# Door_switch.net
KiCad netlist of a schematic drawn in EAGLE
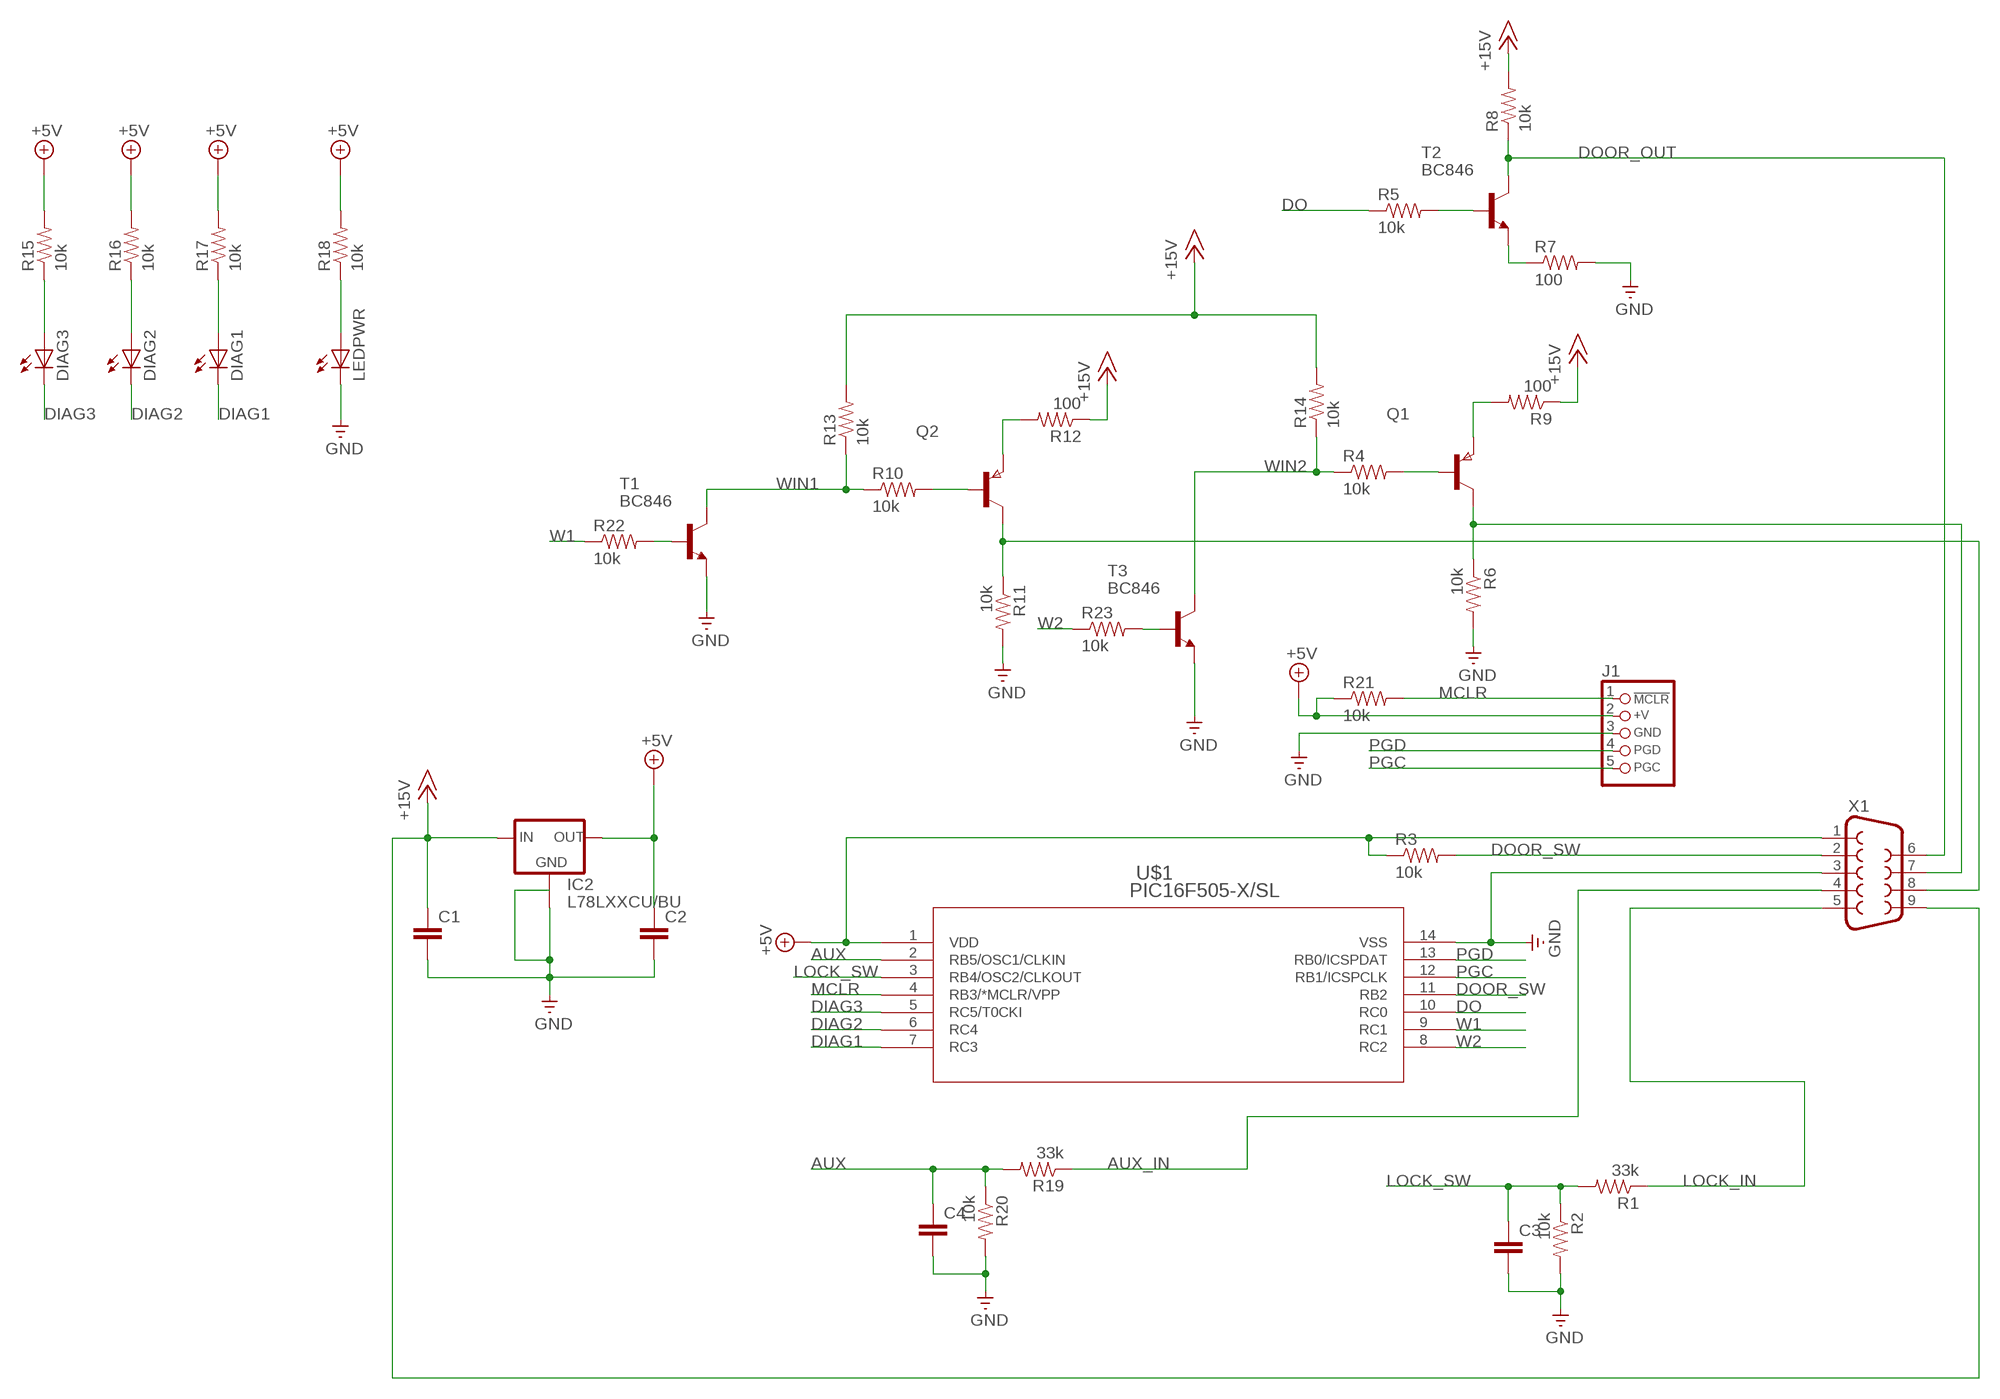
[diagram p0: schematic, sheet 1]

(export (version "E")
  (design (tool "Eeschema 10.0.6"))
  (components
    (comp (ref "C1")
      (value "CC1206")
      (footprint "eagle-import:C1206")
      (libsource (lib "eagle-import") (part "CC1206"))
    )
    (comp (ref "C2")
      (value "CC1206")
      (footprint "eagle-import:C1206")
      (libsource (lib "eagle-import") (part "CC1206"))
    )
    (comp (ref "C3")
      (value "CC1206")
      (footprint "eagle-import:C1206")
      (libsource (lib "eagle-import") (part "CC1206"))
    )
    (comp (ref "C4")
      (value "CC1206")
      (footprint "eagle-import:C1206")
      (libsource (lib "eagle-import") (part "CC1206"))
    )
    (comp (ref "DIAG1")
      (value "LEDCHIP-LED0603")
      (footprint "eagle-import:CHIP-LED0603")
      (libsource (lib "eagle-import") (part "LEDCHIP-LED0603"))
    )
    (comp (ref "DIAG2")
      (value "LEDCHIP-LED0603")
      (footprint "eagle-import:CHIP-LED0603")
      (libsource (lib "eagle-import") (part "LEDCHIP-LED0603"))
    )
    (comp (ref "DIAG3")
      (value "LEDCHIP-LED0603")
      (footprint "eagle-import:CHIP-LED0603")
      (libsource (lib "eagle-import") (part "LEDCHIP-LED0603"))
    )
    (comp (ref "IC2")
      (value "L78LXXCU/BU")
      (footprint "eagle-import:SOT89")
      (libsource (lib "eagle-import") (part "L78LXXCU/BU"))
    )
    (comp (ref "J1")
      (value "CON_HEADER_PRG_PIC_ICSPA")
      (footprint "eagle-import:HEADER_PRG_1X05")
      (libsource (lib "eagle-import") (part "CON_HEADER_PRG_PIC_ICSPA"))
    )
    (comp (ref "LEDPWR")
      (value "LEDCHIP-LED0603")
      (footprint "eagle-import:CHIP-LED0603")
      (libsource (lib "eagle-import") (part "LEDCHIP-LED0603"))
    )
    (comp (ref "Q1")
      (value "PNPSOT23")
      (footprint "eagle-import:SOT-23")
      (fields (field (name "MPN") "DSS20200L-7"))
      (libsource (lib "eagle-import") (part "PNPSOT23"))
    )
    (comp (ref "Q2")
      (value "PNPSOT23")
      (footprint "eagle-import:SOT-23")
      (fields (field (name "MPN") "DSS20200L-7"))
      (libsource (lib "eagle-import") (part "PNPSOT23"))
    )
    (comp (ref "R1")
      (value "33k")
      (footprint "eagle-import:0603-RES")
      (libsource (lib "eagle-import") (part "RESISTOR0603-RES"))
    )
    (comp (ref "R2")
      (value "10k")
      (footprint "eagle-import:0603-RES")
      (libsource (lib "eagle-import") (part "RESISTOR0603-RES"))
    )
    (comp (ref "R3")
      (value "10k")
      (footprint "eagle-import:0603-RES")
      (libsource (lib "eagle-import") (part "RESISTOR0603-RES"))
    )
    (comp (ref "R4")
      (value "10k")
      (footprint "eagle-import:0603-RES")
      (libsource (lib "eagle-import") (part "RESISTOR0603-RES"))
    )
    (comp (ref "R5")
      (value "10k")
      (footprint "eagle-import:0603-RES")
      (libsource (lib "eagle-import") (part "RESISTOR0603-RES"))
    )
    (comp (ref "R6")
      (value "10k")
      (footprint "eagle-import:0603-RES")
      (libsource (lib "eagle-import") (part "RESISTOR0603-RES"))
    )
    (comp (ref "R7")
      (value "100")
      (footprint "eagle-import:0603-RES")
      (libsource (lib "eagle-import") (part "RESISTOR0603-RES"))
    )
    (comp (ref "R8")
      (value "10k")
      (footprint "eagle-import:0603-RES")
      (libsource (lib "eagle-import") (part "RESISTOR0603-RES"))
    )
    (comp (ref "R9")
      (value "100")
      (footprint "eagle-import:0603-RES")
      (libsource (lib "eagle-import") (part "RESISTOR0603-RES"))
    )
    (comp (ref "R10")
      (value "10k")
      (footprint "eagle-import:0603-RES")
      (libsource (lib "eagle-import") (part "RESISTOR0603-RES"))
    )
    (comp (ref "R11")
      (value "10k")
      (footprint "eagle-import:0603-RES")
      (libsource (lib "eagle-import") (part "RESISTOR0603-RES"))
    )
    (comp (ref "R12")
      (value "100")
      (footprint "eagle-import:0603-RES")
      (libsource (lib "eagle-import") (part "RESISTOR0603-RES"))
    )
    (comp (ref "R13")
      (value "10k")
      (footprint "eagle-import:0603-RES")
      (libsource (lib "eagle-import") (part "RESISTOR0603-RES"))
    )
    (comp (ref "R14")
      (value "10k")
      (footprint "eagle-import:0603-RES")
      (libsource (lib "eagle-import") (part "RESISTOR0603-RES"))
    )
    (comp (ref "R15")
      (value "10k")
      (footprint "eagle-import:0603-RES")
      (libsource (lib "eagle-import") (part "RESISTOR0603-RES"))
    )
    (comp (ref "R16")
      (value "10k")
      (footprint "eagle-import:0603-RES")
      (libsource (lib "eagle-import") (part "RESISTOR0603-RES"))
    )
    (comp (ref "R17")
      (value "10k")
      (footprint "eagle-import:0603-RES")
      (libsource (lib "eagle-import") (part "RESISTOR0603-RES"))
    )
    (comp (ref "R18")
      (value "10k")
      (footprint "eagle-import:0603-RES")
      (libsource (lib "eagle-import") (part "RESISTOR0603-RES"))
    )
    (comp (ref "R19")
      (value "33k")
      (footprint "eagle-import:0603-RES")
      (libsource (lib "eagle-import") (part "RESISTOR0603-RES"))
    )
    (comp (ref "R20")
      (value "10k")
      (footprint "eagle-import:0603-RES")
      (libsource (lib "eagle-import") (part "RESISTOR0603-RES"))
    )
    (comp (ref "R21")
      (value "10k")
      (footprint "eagle-import:0603-RES")
      (libsource (lib "eagle-import") (part "RESISTOR0603-RES"))
    )
    (comp (ref "R22")
      (value "10k")
      (footprint "eagle-import:0603-RES")
      (libsource (lib "eagle-import") (part "RESISTOR0603-RES"))
    )
    (comp (ref "R23")
      (value "10k")
      (footprint "eagle-import:0603-RES")
      (libsource (lib "eagle-import") (part "RESISTOR0603-RES"))
    )
    (comp (ref "T1")
      (value "BC846")
      (footprint "eagle-import:SOT23")
      (libsource (lib "eagle-import") (part "BC846"))
    )
    (comp (ref "T2")
      (value "BC846")
      (footprint "eagle-import:SOT23")
      (libsource (lib "eagle-import") (part "BC846"))
    )
    (comp (ref "T3")
      (value "BC846")
      (footprint "eagle-import:SOT23")
      (libsource (lib "eagle-import") (part "BC846"))
    )
    (comp (ref "U$1")
      (value "PIC16F505-X/SL")
      (footprint "eagle-import:SOIC14-N_MC")
      (libsource (lib "eagle-import") (part "PIC16F505-X/SL"))
    )
    (comp (ref "X1")
      (value "F09HP")
      (footprint "eagle-import:F09HP")
      (libsource (lib "eagle-import") (part "F09HP"))
    )
  )
  (nets
    (net (code "1") (name "+5V") (class "Default")
      (node (ref "C2") (pin "1") (pinfunction "1_1") (pintype "passive"))
      (node (ref "IC2") (pin "1") (pinfunction "OUT_1") (pintype "passive"))
      (node (ref "J1") (pin "2") (pinfunction "+V_2") (pintype "passive"))
      (node (ref "R15") (pin "2") (pinfunction "2_2") (pintype "passive"))
      (node (ref "R16") (pin "2") (pinfunction "2_2") (pintype "passive"))
      (node (ref "R17") (pin "2") (pinfunction "2_2") (pintype "passive"))
      (node (ref "R18") (pin "2") (pinfunction "2_2") (pintype "passive"))
      (node (ref "R21") (pin "1") (pinfunction "1_1") (pintype "passive"))
      (node (ref "R3") (pin "1") (pinfunction "1_1") (pintype "passive"))
      (node (ref "U$1") (pin "1") (pinfunction "VDD_1") (pintype "passive"))
      (node (ref "X1") (pin "1") (pinfunction "1_1") (pintype "passive"))
    )
    (net (code "2") (name "+15V") (class "Default")
      (node (ref "C1") (pin "1") (pinfunction "1_1") (pintype "passive"))
      (node (ref "IC2") (pin "3") (pinfunction "IN_3") (pintype "input"))
      (node (ref "R12") (pin "1") (pinfunction "1_1") (pintype "passive"))
      (node (ref "R13") (pin "2") (pinfunction "2_2") (pintype "passive"))
      (node (ref "R14") (pin "2") (pinfunction "2_2") (pintype "passive"))
      (node (ref "R8") (pin "2") (pinfunction "2_2") (pintype "passive"))
      (node (ref "R9") (pin "1") (pinfunction "1_1") (pintype "passive"))
      (node (ref "X1") (pin "9") (pinfunction "9_9") (pintype "passive"))
    )
    (net (code "3") (name "/AUX") (class "Default")
      (node (ref "C4") (pin "1") (pinfunction "1_1") (pintype "passive"))
      (node (ref "R19") (pin "2") (pinfunction "2_2") (pintype "passive"))
      (node (ref "R20") (pin "1") (pinfunction "1_1") (pintype "passive"))
      (node (ref "U$1") (pin "2") (pinfunction "RB5/OSC1/CLKIN_2") (pintype "passive"))
    )
    (net (code "4") (name "/AUX_IN") (class "Default")
      (node (ref "R19") (pin "1") (pinfunction "1_1") (pintype "passive"))
      (node (ref "X1") (pin "4") (pinfunction "4_4") (pintype "passive"))
    )
    (net (code "5") (name "/DIAG1") (class "Default")
      (node (ref "DIAG1") (pin "C") (pinfunction "C_C") (pintype "passive"))
      (node (ref "U$1") (pin "7") (pinfunction "RC3_7") (pintype "passive"))
    )
    (net (code "6") (name "/DIAG2") (class "Default")
      (node (ref "DIAG2") (pin "C") (pinfunction "C_C") (pintype "passive"))
      (node (ref "U$1") (pin "6") (pinfunction "RC4_6") (pintype "passive"))
    )
    (net (code "7") (name "/DIAG3") (class "Default")
      (node (ref "DIAG3") (pin "C") (pinfunction "C_C") (pintype "passive"))
      (node (ref "U$1") (pin "5") (pinfunction "RC5/T0CKI_5") (pintype "passive"))
    )
    (net (code "8") (name "/DO") (class "Default")
      (node (ref "R5") (pin "1") (pinfunction "1_1") (pintype "passive"))
      (node (ref "U$1") (pin "10") (pinfunction "RC0_10") (pintype "passive"))
    )
    (net (code "9") (name "/DOOR_OUT") (class "Default")
      (node (ref "R8") (pin "1") (pinfunction "1_1") (pintype "passive"))
      (node (ref "T2") (pin "3") (pinfunction "C_3") (pintype "passive"))
      (node (ref "X1") (pin "6") (pinfunction "6_6") (pintype "passive"))
    )
    (net (code "10") (name "/DOOR_SW") (class "Default")
      (node (ref "R3") (pin "2") (pinfunction "2_2") (pintype "passive"))
      (node (ref "U$1") (pin "11") (pinfunction "RB2_11") (pintype "passive"))
      (node (ref "X1") (pin "2") (pinfunction "2_2") (pintype "passive"))
    )
    (net (code "11") (name "/LOCK_IN") (class "Default")
      (node (ref "R1") (pin "1") (pinfunction "1_1") (pintype "passive"))
      (node (ref "X1") (pin "5") (pinfunction "5_5") (pintype "passive"))
    )
    (net (code "12") (name "/LOCK_SW") (class "Default")
      (node (ref "C3") (pin "1") (pinfunction "1_1") (pintype "passive"))
      (node (ref "R1") (pin "2") (pinfunction "2_2") (pintype "passive"))
      (node (ref "R2") (pin "1") (pinfunction "1_1") (pintype "passive"))
      (node (ref "U$1") (pin "3") (pinfunction "RB4/OSC2/CLKOUT_3") (pintype "passive"))
    )
    (net (code "13") (name "/MCLR") (class "Default")
      (node (ref "J1") (pin "1") (pinfunction "/MCLR_1") (pintype "passive"))
      (node (ref "R21") (pin "2") (pinfunction "2_2") (pintype "passive"))
      (node (ref "U$1") (pin "4") (pinfunction "RB3/*MCLR/VPP_4") (pintype "passive"))
    )
    (net (code "14") (name "/PGC") (class "Default")
      (node (ref "J1") (pin "5") (pinfunction "PGC_5") (pintype "passive"))
      (node (ref "U$1") (pin "12") (pinfunction "RB1/ICSPCLK_12") (pintype "passive"))
    )
    (net (code "15") (name "/PGD") (class "Default")
      (node (ref "J1") (pin "4") (pinfunction "PGD_4") (pintype "passive"))
      (node (ref "U$1") (pin "13") (pinfunction "RB0/ICSPDAT_13") (pintype "passive"))
    )
    (net (code "16") (name "/W1") (class "Default")
      (node (ref "R22") (pin "1") (pinfunction "1_1") (pintype "passive"))
      (node (ref "U$1") (pin "9") (pinfunction "RC1_9") (pintype "passive"))
    )
    (net (code "17") (name "/W2") (class "Default")
      (node (ref "R23") (pin "1") (pinfunction "1_1") (pintype "passive"))
      (node (ref "U$1") (pin "8") (pinfunction "RC2_8") (pintype "passive"))
    )
    (net (code "18") (name "/WIN1") (class "Default")
      (node (ref "R10") (pin "1") (pinfunction "1_1") (pintype "passive"))
      (node (ref "R13") (pin "1") (pinfunction "1_1") (pintype "passive"))
      (node (ref "T1") (pin "3") (pinfunction "C_3") (pintype "passive"))
    )
    (net (code "19") (name "/WIN2") (class "Default")
      (node (ref "R14") (pin "1") (pinfunction "1_1") (pintype "passive"))
      (node (ref "R4") (pin "1") (pinfunction "1_1") (pintype "passive"))
      (node (ref "T3") (pin "3") (pinfunction "C_3") (pintype "passive"))
    )
    (net (code "20") (name "GND") (class "Default")
      (node (ref "C1") (pin "2") (pinfunction "2_2") (pintype "passive"))
      (node (ref "C2") (pin "2") (pinfunction "2_2") (pintype "passive"))
      (node (ref "C3") (pin "2") (pinfunction "2_2") (pintype "passive"))
      (node (ref "C4") (pin "2") (pinfunction "2_2") (pintype "passive"))
      (node (ref "IC2") (pin "2") (pinfunction "GND_2") (pintype "input"))
      (node (ref "IC2") (pin "4") (pinfunction "GND1_4") (pintype "input"))
      (node (ref "J1") (pin "3") (pinfunction "GND_3") (pintype "passive"))
      (node (ref "LEDPWR") (pin "C") (pinfunction "C_C") (pintype "passive"))
      (node (ref "R11") (pin "2") (pinfunction "2_2") (pintype "passive"))
      (node (ref "R2") (pin "2") (pinfunction "2_2") (pintype "passive"))
      (node (ref "R20") (pin "2") (pinfunction "2_2") (pintype "passive"))
      (node (ref "R6") (pin "2") (pinfunction "2_2") (pintype "passive"))
      (node (ref "R7") (pin "2") (pinfunction "2_2") (pintype "passive"))
      (node (ref "T1") (pin "2") (pinfunction "E_2") (pintype "passive"))
      (node (ref "T3") (pin "2") (pinfunction "E_2") (pintype "passive"))
      (node (ref "U$1") (pin "14") (pinfunction "VSS_14") (pintype "passive"))
      (node (ref "X1") (pin "3") (pinfunction "3_3") (pintype "passive"))
    )
    (net (code "21") (name "Net-(DIAG1-PadA)") (class "Default")
      (node (ref "DIAG1") (pin "A") (pinfunction "A_A") (pintype "passive"))
      (node (ref "R17") (pin "1") (pinfunction "1_1") (pintype "passive"))
    )
    (net (code "22") (name "Net-(DIAG2-PadA)") (class "Default")
      (node (ref "DIAG2") (pin "A") (pinfunction "A_A") (pintype "passive"))
      (node (ref "R16") (pin "1") (pinfunction "1_1") (pintype "passive"))
    )
    (net (code "23") (name "Net-(DIAG3-PadA)") (class "Default")
      (node (ref "DIAG3") (pin "A") (pinfunction "A_A") (pintype "passive"))
      (node (ref "R15") (pin "1") (pinfunction "1_1") (pintype "passive"))
    )
    (net (code "24") (name "Net-(LEDPWR-PadA)") (class "Default")
      (node (ref "LEDPWR") (pin "A") (pinfunction "A_A") (pintype "passive"))
      (node (ref "R18") (pin "1") (pinfunction "1_1") (pintype "passive"))
    )
    (net (code "25") (name "Net-(Q1-B)") (class "Default")
      (node (ref "Q1") (pin "3") (pinfunction "B_3") (pintype "passive"))
      (node (ref "R4") (pin "2") (pinfunction "2_2") (pintype "passive"))
    )
    (net (code "26") (name "Net-(Q1-C)") (class "Default")
      (node (ref "Q1") (pin "1") (pinfunction "C_1") (pintype "passive"))
      (node (ref "R6") (pin "1") (pinfunction "1_1") (pintype "passive"))
      (node (ref "X1") (pin "7") (pinfunction "7_7") (pintype "passive"))
    )
    (net (code "27") (name "Net-(Q1-E)") (class "Default")
      (node (ref "Q1") (pin "2") (pinfunction "E_2") (pintype "passive"))
      (node (ref "R9") (pin "2") (pinfunction "2_2") (pintype "passive"))
    )
    (net (code "28") (name "Net-(Q2-B)") (class "Default")
      (node (ref "Q2") (pin "3") (pinfunction "B_3") (pintype "passive"))
      (node (ref "R10") (pin "2") (pinfunction "2_2") (pintype "passive"))
    )
    (net (code "29") (name "Net-(Q2-C)") (class "Default")
      (node (ref "Q2") (pin "1") (pinfunction "C_1") (pintype "passive"))
      (node (ref "R11") (pin "1") (pinfunction "1_1") (pintype "passive"))
      (node (ref "X1") (pin "8") (pinfunction "8_8") (pintype "passive"))
    )
    (net (code "30") (name "Net-(Q2-E)") (class "Default")
      (node (ref "Q2") (pin "2") (pinfunction "E_2") (pintype "passive"))
      (node (ref "R12") (pin "2") (pinfunction "2_2") (pintype "passive"))
    )
    (net (code "31") (name "Net-(T1-B)") (class "Default")
      (node (ref "R22") (pin "2") (pinfunction "2_2") (pintype "passive"))
      (node (ref "T1") (pin "1") (pinfunction "B_1") (pintype "passive"))
    )
    (net (code "32") (name "Net-(T2-B)") (class "Default")
      (node (ref "R5") (pin "2") (pinfunction "2_2") (pintype "passive"))
      (node (ref "T2") (pin "1") (pinfunction "B_1") (pintype "passive"))
    )
    (net (code "33") (name "Net-(T2-E)") (class "Default")
      (node (ref "R7") (pin "1") (pinfunction "1_1") (pintype "passive"))
      (node (ref "T2") (pin "2") (pinfunction "E_2") (pintype "passive"))
    )
    (net (code "34") (name "Net-(T3-B)") (class "Default")
      (node (ref "R23") (pin "2") (pinfunction "2_2") (pintype "passive"))
      (node (ref "T3") (pin "1") (pinfunction "B_1") (pintype "passive"))
    )
  )
)
